# kartusho.net
KiCad netlist of a schematic drawn in EAGLE
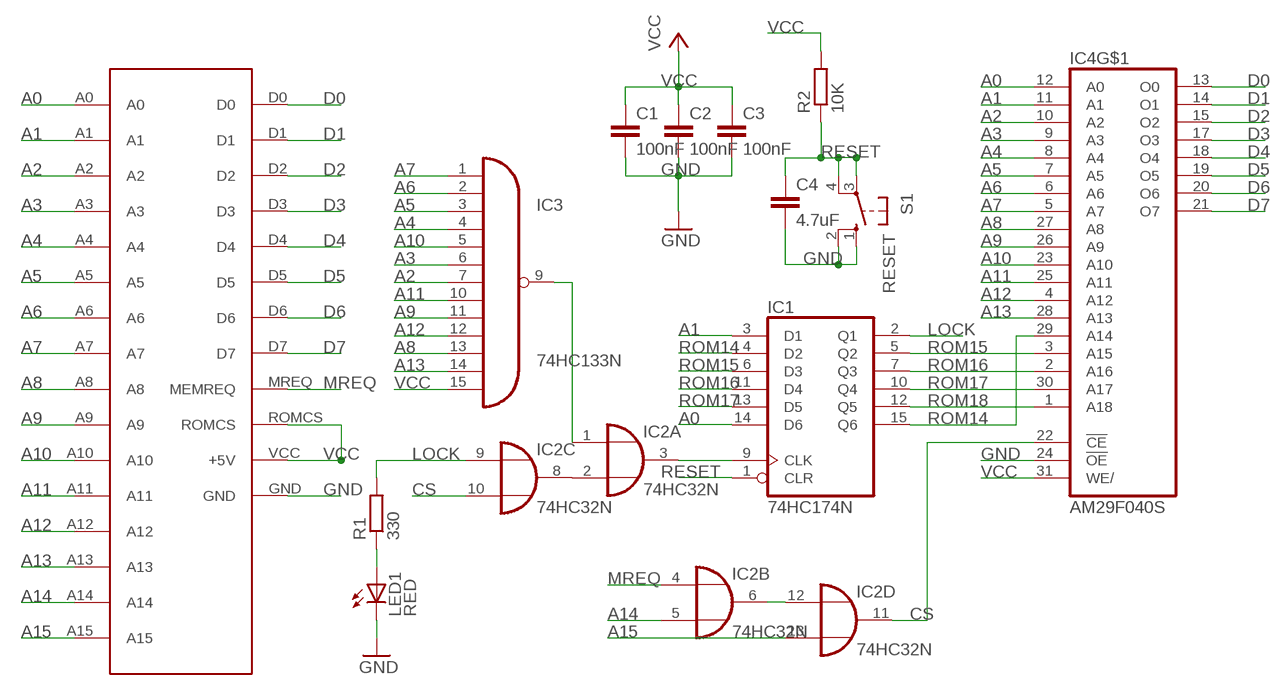
[diagram p0: schematic, sheet 1]

(export (version "E")
  (design (tool "Eeschema 10.0.6"))
  (components
    (comp (ref "C1")
      (value "100nF")
      (footprint "eagle-import:C050-025X075")
      (libsource (lib "eagle-import") (part "C-EU050-025X075"))
    )
    (comp (ref "C2")
      (value "100nF")
      (footprint "eagle-import:C025-025X050")
      (libsource (lib "eagle-import") (part "C-EU025-025X050"))
    )
    (comp (ref "C3")
      (value "100nF")
      (footprint "eagle-import:C050-025X075")
      (libsource (lib "eagle-import") (part "C-EU050-025X075"))
    )
    (comp (ref "C4")
      (value "4.7uF")
      (footprint "eagle-import:C025-025X050")
      (libsource (lib "eagle-import") (part "C-EU025-025X050"))
    )
    (comp (ref "IC1")
      (value "74HC174N")
      (footprint "eagle-import:DIL16")
      (libsource (lib "eagle-import") (part "74174NHC"))
    )
    (comp (ref "IC2")
      (value "74HC32N")
      (footprint "eagle-import:DIL14")
      (libsource (lib "eagle-import") (part "7432NHC"))
    )
    (comp (ref "IC3")
      (value "74HC133N")
      (footprint "eagle-import:DIL16")
      (libsource (lib "eagle-import") (part "74133NHC"))
    )
    (comp (ref "IC4")
      (value "AM29F040S")
      (footprint "eagle-import:PLCC-SR32")
      (libsource (lib "eagle-import") (part "AM29F040S"))
    )
    (comp (ref "LED1")
      (value "RED")
      (footprint "eagle-import:LED3MM")
      (libsource (lib "eagle-import") (part "LED3MM"))
    )
    (comp (ref "R1")
      (value "330")
      (footprint "eagle-import:0204_7")
      (libsource (lib "eagle-import") (part "R-EU_0204/7"))
    )
    (comp (ref "R2")
      (value "10K")
      (footprint "eagle-import:0204_7")
      (libsource (lib "eagle-import") (part "R-EU_0204/7"))
    )
    (comp (ref "S1")
      (value "RESET")
      (footprint "eagle-import:B3F-10XX")
      (fields (field (name "MPN") "B3F-1000"))
      (libsource (lib "eagle-import") (part "10-XX"))
    )
    (comp (ref "U$1")
      (value "IF2BUS")
      (footprint "eagle-import:BUS_CARTUCHO_IF2")
      (libsource (lib "eagle-import") (part "IF2BUS"))
    )
  )
  (nets
    (net (code "1") (name "/A0") (class "Default")
      (node (ref "IC1") (pin "14") (pinfunction "D6_14") (pintype "input"))
      (node (ref "IC4") (pin "12") (pinfunction "A0_12") (pintype "input"))
      (node (ref "U$1") (pin "A0") (pinfunction "A0_A0") (pintype "bidirectional"))
    )
    (net (code "2") (name "/A1") (class "Default")
      (node (ref "IC1") (pin "3") (pinfunction "D1_3") (pintype "input"))
      (node (ref "IC4") (pin "11") (pinfunction "A1_11") (pintype "input"))
      (node (ref "U$1") (pin "A1") (pinfunction "A1_A1") (pintype "bidirectional"))
    )
    (net (code "3") (name "/A2") (class "Default")
      (node (ref "IC3") (pin "7") (pinfunction "I6_7") (pintype "input"))
      (node (ref "IC4") (pin "10") (pinfunction "A2_10") (pintype "input"))
      (node (ref "U$1") (pin "A2") (pinfunction "A2_A2") (pintype "bidirectional"))
    )
    (net (code "4") (name "/A3") (class "Default")
      (node (ref "IC3") (pin "6") (pinfunction "I5_6") (pintype "input"))
      (node (ref "IC4") (pin "9") (pinfunction "A3_9") (pintype "input"))
      (node (ref "U$1") (pin "A3") (pinfunction "A3_A3") (pintype "bidirectional"))
    )
    (net (code "5") (name "/A4") (class "Default")
      (node (ref "IC3") (pin "4") (pinfunction "I3_4") (pintype "input"))
      (node (ref "IC4") (pin "8") (pinfunction "A4_8") (pintype "input"))
      (node (ref "U$1") (pin "A4") (pinfunction "A4_A4") (pintype "bidirectional"))
    )
    (net (code "6") (name "/A5") (class "Default")
      (node (ref "IC3") (pin "3") (pinfunction "I2_3") (pintype "input"))
      (node (ref "IC4") (pin "7") (pinfunction "A5_7") (pintype "input"))
      (node (ref "U$1") (pin "A5") (pinfunction "A5_A5") (pintype "bidirectional"))
    )
    (net (code "7") (name "/A6") (class "Default")
      (node (ref "IC3") (pin "2") (pinfunction "I1_2") (pintype "input"))
      (node (ref "IC4") (pin "6") (pinfunction "A6_6") (pintype "input"))
      (node (ref "U$1") (pin "A6") (pinfunction "A6_A6") (pintype "bidirectional"))
    )
    (net (code "8") (name "/A7") (class "Default")
      (node (ref "IC3") (pin "1") (pinfunction "I0_1") (pintype "input"))
      (node (ref "IC4") (pin "5") (pinfunction "A7_5") (pintype "input"))
      (node (ref "U$1") (pin "A7") (pinfunction "A7_A7") (pintype "bidirectional"))
    )
    (net (code "9") (name "/A8") (class "Default")
      (node (ref "IC3") (pin "13") (pinfunction "I10_13") (pintype "input"))
      (node (ref "IC4") (pin "27") (pinfunction "A8_27") (pintype "input"))
      (node (ref "U$1") (pin "A8") (pinfunction "A8_A8") (pintype "bidirectional"))
    )
    (net (code "10") (name "/A9") (class "Default")
      (node (ref "IC3") (pin "11") (pinfunction "I8_11") (pintype "input"))
      (node (ref "IC4") (pin "26") (pinfunction "A9_26") (pintype "input"))
      (node (ref "U$1") (pin "A9") (pinfunction "A9_A9") (pintype "bidirectional"))
    )
    (net (code "11") (name "/A10") (class "Default")
      (node (ref "IC3") (pin "5") (pinfunction "I4_5") (pintype "input"))
      (node (ref "IC4") (pin "23") (pinfunction "A10_23") (pintype "input"))
      (node (ref "U$1") (pin "A10") (pinfunction "A10_A10") (pintype "bidirectional"))
    )
    (net (code "12") (name "/A11") (class "Default")
      (node (ref "IC3") (pin "10") (pinfunction "I7_10") (pintype "input"))
      (node (ref "IC4") (pin "25") (pinfunction "A11_25") (pintype "input"))
      (node (ref "U$1") (pin "A11") (pinfunction "A11_A11") (pintype "bidirectional"))
    )
    (net (code "13") (name "/A12") (class "Default")
      (node (ref "IC3") (pin "12") (pinfunction "I9_12") (pintype "input"))
      (node (ref "IC4") (pin "4") (pinfunction "A12_4") (pintype "input"))
      (node (ref "U$1") (pin "A12") (pinfunction "A12_A12") (pintype "bidirectional"))
    )
    (net (code "14") (name "/A13") (class "Default")
      (node (ref "IC3") (pin "14") (pinfunction "I11_14") (pintype "input"))
      (node (ref "IC4") (pin "28") (pinfunction "A13_28") (pintype "input"))
      (node (ref "U$1") (pin "A13") (pinfunction "A13_A13") (pintype "bidirectional"))
    )
    (net (code "15") (name "/A14") (class "Default")
      (node (ref "IC2") (pin "5") (pinfunction "I1_5") (pintype "input"))
      (node (ref "U$1") (pin "A14") (pinfunction "A14_A14") (pintype "bidirectional"))
    )
    (net (code "16") (name "/A15") (class "Default")
      (node (ref "IC2") (pin "13") (pinfunction "I1_13") (pintype "input"))
      (node (ref "U$1") (pin "A15") (pinfunction "A15_A15") (pintype "bidirectional"))
    )
    (net (code "17") (name "/CS") (class "Default")
      (node (ref "IC2") (pin "10") (pinfunction "I1_10") (pintype "input"))
      (node (ref "IC2") (pin "11") (pinfunction "O_11") (pintype "output"))
      (node (ref "IC4") (pin "22") (pinfunction "~{CE}_22") (pintype "input"))
    )
    (net (code "18") (name "/D0") (class "Default")
      (node (ref "IC4") (pin "13") (pinfunction "O0_13") (pintype "tri_state"))
      (node (ref "U$1") (pin "D0") (pinfunction "D0_D0") (pintype "bidirectional"))
    )
    (net (code "19") (name "/D1") (class "Default")
      (node (ref "IC4") (pin "14") (pinfunction "O1_14") (pintype "tri_state"))
      (node (ref "U$1") (pin "D1") (pinfunction "D1_D1") (pintype "bidirectional"))
    )
    (net (code "20") (name "/D2") (class "Default")
      (node (ref "IC4") (pin "15") (pinfunction "O2_15") (pintype "tri_state"))
      (node (ref "U$1") (pin "D2") (pinfunction "D2_D2") (pintype "bidirectional"))
    )
    (net (code "21") (name "/D3") (class "Default")
      (node (ref "IC4") (pin "17") (pinfunction "O3_17") (pintype "tri_state"))
      (node (ref "U$1") (pin "D3") (pinfunction "D3_D3") (pintype "bidirectional"))
    )
    (net (code "22") (name "/D4") (class "Default")
      (node (ref "IC4") (pin "18") (pinfunction "O4_18") (pintype "tri_state"))
      (node (ref "U$1") (pin "D4") (pinfunction "D4_D4") (pintype "bidirectional"))
    )
    (net (code "23") (name "/D5") (class "Default")
      (node (ref "IC4") (pin "19") (pinfunction "O5_19") (pintype "tri_state"))
      (node (ref "U$1") (pin "D5") (pinfunction "D5_D5") (pintype "bidirectional"))
    )
    (net (code "24") (name "/D6") (class "Default")
      (node (ref "IC4") (pin "20") (pinfunction "O6_20") (pintype "tri_state"))
      (node (ref "U$1") (pin "D6") (pinfunction "D6_D6") (pintype "bidirectional"))
    )
    (net (code "25") (name "/D7") (class "Default")
      (node (ref "IC4") (pin "21") (pinfunction "O7_21") (pintype "tri_state"))
      (node (ref "U$1") (pin "D7") (pinfunction "D7_D7") (pintype "bidirectional"))
    )
    (net (code "26") (name "/LOCK") (class "Default")
      (node (ref "IC1") (pin "2") (pinfunction "Q1_2") (pintype "output"))
      (node (ref "IC2") (pin "9") (pinfunction "I0_9") (pintype "input"))
      (node (ref "R1") (pin "2") (pinfunction "2_2") (pintype "passive"))
    )
    (net (code "27") (name "/MREQ") (class "Default")
      (node (ref "IC2") (pin "4") (pinfunction "I0_4") (pintype "input"))
      (node (ref "U$1") (pin "MREQ") (pinfunction "MEMREQ_MREQ") (pintype "bidirectional"))
    )
    (net (code "28") (name "/RESET") (class "Default")
      (node (ref "C4") (pin "1") (pinfunction "1_1") (pintype "passive"))
      (node (ref "IC1") (pin "1") (pinfunction "CLR_1") (pintype "input"))
      (node (ref "R2") (pin "1") (pinfunction "1_1") (pintype "passive"))
      (node (ref "S1") (pin "3") (pinfunction "P_3") (pintype "passive"))
      (node (ref "S1") (pin "4") (pinfunction "P1_4") (pintype "passive"))
    )
    (net (code "29") (name "/ROM14") (class "Default")
      (node (ref "IC1") (pin "15") (pinfunction "Q6_15") (pintype "output"))
      (node (ref "IC1") (pin "4") (pinfunction "D2_4") (pintype "input"))
      (node (ref "IC4") (pin "29") (pinfunction "A14_29") (pintype "input"))
    )
    (net (code "30") (name "/ROM15") (class "Default")
      (node (ref "IC1") (pin "5") (pinfunction "Q2_5") (pintype "output"))
      (node (ref "IC1") (pin "6") (pinfunction "D3_6") (pintype "input"))
      (node (ref "IC4") (pin "3") (pinfunction "A15_3") (pintype "input"))
    )
    (net (code "31") (name "/ROM16") (class "Default")
      (node (ref "IC1") (pin "11") (pinfunction "D4_11") (pintype "input"))
      (node (ref "IC1") (pin "7") (pinfunction "Q3_7") (pintype "output"))
      (node (ref "IC4") (pin "2") (pinfunction "A16_2") (pintype "input"))
    )
    (net (code "32") (name "/ROM17") (class "Default")
      (node (ref "IC1") (pin "10") (pinfunction "Q4_10") (pintype "output"))
      (node (ref "IC1") (pin "13") (pinfunction "D5_13") (pintype "input"))
      (node (ref "IC4") (pin "30") (pinfunction "A17_30") (pintype "input"))
    )
    (net (code "33") (name "/ROM18") (class "Default")
      (node (ref "IC1") (pin "12") (pinfunction "Q5_12") (pintype "output"))
      (node (ref "IC4") (pin "1") (pinfunction "A18_1") (pintype "input"))
    )
    (net (code "34") (name "GND") (class "Default")
      (node (ref "C1") (pin "2") (pinfunction "2_2") (pintype "passive"))
      (node (ref "C2") (pin "2") (pinfunction "2_2") (pintype "passive"))
      (node (ref "C3") (pin "2") (pinfunction "2_2") (pintype "passive"))
      (node (ref "C4") (pin "2") (pinfunction "2_2") (pintype "passive"))
      (node (ref "IC4") (pin "24") (pinfunction "~{OE}_24") (pintype "input"))
      (node (ref "LED1") (pin "K") (pinfunction "C_K") (pintype "passive"))
      (node (ref "S1") (pin "1") (pinfunction "S_1") (pintype "passive"))
      (node (ref "S1") (pin "2") (pinfunction "S1_2") (pintype "passive"))
      (node (ref "U$1") (pin "GND") (pinfunction "GND_GND") (pintype "bidirectional"))
    )
    (net (code "35") (name "Net-(IC1A-CLK)") (class "Default")
      (node (ref "IC1") (pin "9") (pinfunction "CLK_9") (pintype "input"))
      (node (ref "IC2") (pin "3") (pinfunction "O_3") (pintype "output"))
    )
    (net (code "36") (name "Net-(IC2A-I0)") (class "Default")
      (node (ref "IC2") (pin "1") (pinfunction "I0_1") (pintype "input"))
      (node (ref "IC3") (pin "9") (pinfunction "O_9") (pintype "output"))
    )
    (net (code "37") (name "Net-(IC2A-I1)") (class "Default")
      (node (ref "IC2") (pin "2") (pinfunction "I1_2") (pintype "input"))
      (node (ref "IC2") (pin "8") (pinfunction "O_8") (pintype "output"))
    )
    (net (code "38") (name "Net-(IC2B-O)") (class "Default")
      (node (ref "IC2") (pin "12") (pinfunction "I0_12") (pintype "input"))
      (node (ref "IC2") (pin "6") (pinfunction "O_6") (pintype "output"))
    )
    (net (code "39") (name "Net-(LED1-PadA)") (class "Default")
      (node (ref "LED1") (pin "A") (pinfunction "A_A") (pintype "passive"))
      (node (ref "R1") (pin "1") (pinfunction "1_1") (pintype "passive"))
    )
    (net (code "40") (name "VCC") (class "Default")
      (node (ref "C1") (pin "1") (pinfunction "1_1") (pintype "passive"))
      (node (ref "C2") (pin "1") (pinfunction "1_1") (pintype "passive"))
      (node (ref "C3") (pin "1") (pinfunction "1_1") (pintype "passive"))
      (node (ref "IC3") (pin "15") (pinfunction "I12_15") (pintype "input"))
      (node (ref "IC4") (pin "31") (pinfunction "WE/_31") (pintype "input"))
      (node (ref "R2") (pin "2") (pinfunction "2_2") (pintype "passive"))
      (node (ref "U$1") (pin "ROMCS") (pinfunction "ROMCS_ROMCS") (pintype "bidirectional"))
      (node (ref "U$1") (pin "VCC") (pinfunction "+5V_VCC") (pintype "bidirectional"))
    )
  )
)
